# FOURCHANNEL_REAY_DRIVER.net
KiCad netlist of a schematic drawn in EAGLE
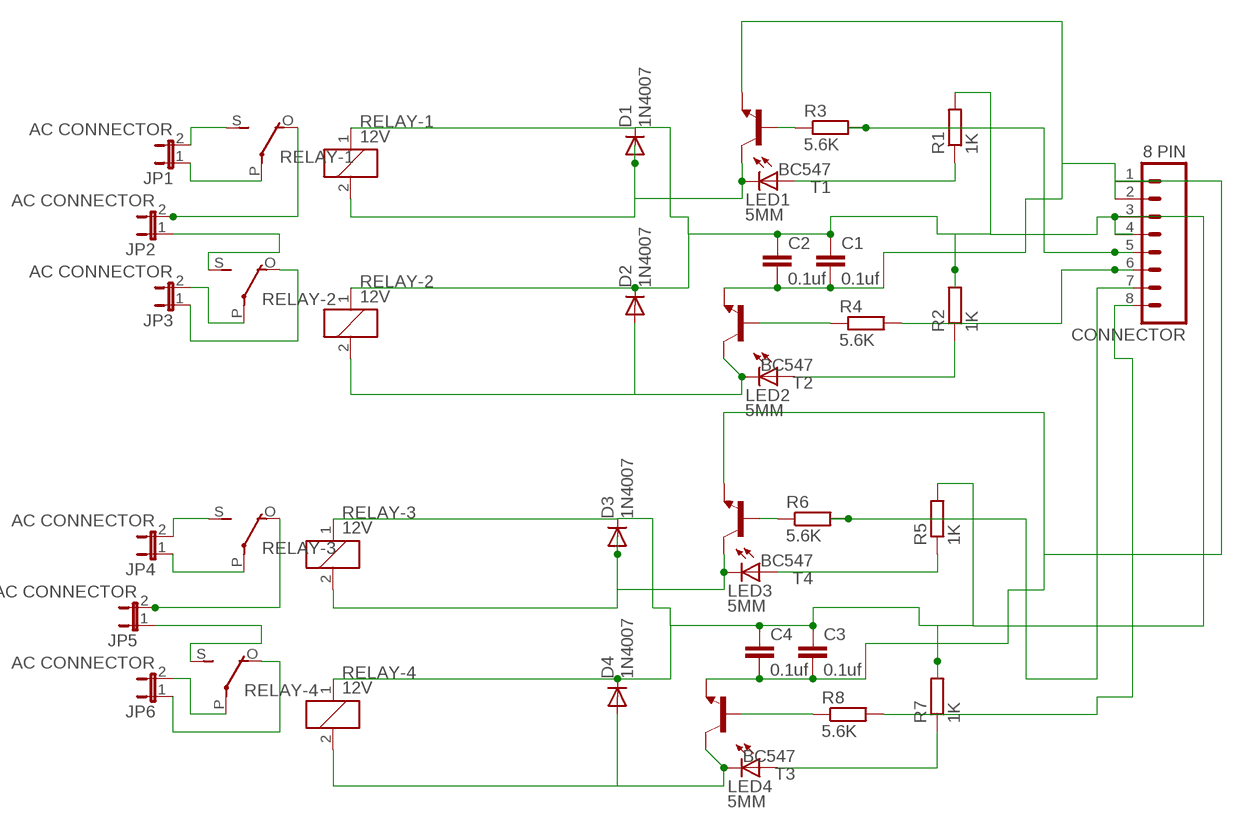
[diagram p0: schematic, sheet 1]

(export (version "E")
  (design (tool "Eeschema 10.0.6"))
  (components
    (comp (ref "C1")
      (value "0.1uf")
      (footprint "eagle-import:C2.5-3")
      (libsource (lib "eagle-import") (part "C2,5-3"))
    )
    (comp (ref "C2")
      (value "0.1uf")
      (footprint "eagle-import:C2.5-3")
      (libsource (lib "eagle-import") (part "C2,5-3"))
    )
    (comp (ref "C3")
      (value "0.1uf")
      (footprint "eagle-import:C2.5-3")
      (libsource (lib "eagle-import") (part "C2,5-3"))
    )
    (comp (ref "C4")
      (value "0.1uf")
      (footprint "eagle-import:C2.5-3")
      (libsource (lib "eagle-import") (part "C2,5-3"))
    )
    (comp (ref "CONNECTOR")
      (value "8 PIN")
      (footprint "eagle-import:08P")
      (libsource (lib "eagle-import") (part "M08"))
    )
    (comp (ref "D1")
      (value "1N4007")
      (footprint "eagle-import:DO41-10")
      (libsource (lib "eagle-import") (part "1N4004"))
    )
    (comp (ref "D2")
      (value "1N4007")
      (footprint "eagle-import:DO41-10")
      (libsource (lib "eagle-import") (part "1N4004"))
    )
    (comp (ref "D3")
      (value "1N4007")
      (footprint "eagle-import:DO41-10")
      (libsource (lib "eagle-import") (part "1N4004"))
    )
    (comp (ref "D4")
      (value "1N4007")
      (footprint "eagle-import:DO41-10")
      (libsource (lib "eagle-import") (part "1N4004"))
    )
    (comp (ref "JP1")
      (value "AC CONNECTOR")
      (footprint "eagle-import:JP1")
      (libsource (lib "eagle-import") (part "JP1E"))
    )
    (comp (ref "JP2")
      (value "AC CONNECTOR")
      (footprint "eagle-import:JP1")
      (libsource (lib "eagle-import") (part "JP1E"))
    )
    (comp (ref "JP3")
      (value "AC CONNECTOR")
      (footprint "eagle-import:JP1")
      (libsource (lib "eagle-import") (part "JP1E"))
    )
    (comp (ref "JP4")
      (value "AC CONNECTOR")
      (footprint "eagle-import:JP1")
      (libsource (lib "eagle-import") (part "JP1E"))
    )
    (comp (ref "JP5")
      (value "AC CONNECTOR")
      (footprint "eagle-import:JP1")
      (libsource (lib "eagle-import") (part "JP1E"))
    )
    (comp (ref "JP6")
      (value "AC CONNECTOR")
      (footprint "eagle-import:JP1")
      (libsource (lib "eagle-import") (part "JP1E"))
    )
    (comp (ref "LED1")
      (value "5MM")
      (footprint "eagle-import:LED5MM")
      (libsource (lib "eagle-import") (part "LED5MM"))
    )
    (comp (ref "LED2")
      (value "5MM")
      (footprint "eagle-import:LED5MM")
      (libsource (lib "eagle-import") (part "LED5MM"))
    )
    (comp (ref "LED3")
      (value "5MM")
      (footprint "eagle-import:LED5MM")
      (libsource (lib "eagle-import") (part "LED5MM"))
    )
    (comp (ref "LED4")
      (value "5MM")
      (footprint "eagle-import:LED5MM")
      (libsource (lib "eagle-import") (part "LED5MM"))
    )
    (comp (ref "R1")
      (value "1K")
      (footprint "eagle-import:0204_7")
      (libsource (lib "eagle-import") (part "R-EU_0204/7"))
    )
    (comp (ref "R2")
      (value "1K")
      (footprint "eagle-import:0204_7")
      (libsource (lib "eagle-import") (part "R-EU_0204/7"))
    )
    (comp (ref "R3")
      (value "5.6K")
      (footprint "eagle-import:0204_7")
      (libsource (lib "eagle-import") (part "R-EU_0204/7"))
    )
    (comp (ref "R4")
      (value "5.6K")
      (footprint "eagle-import:0204_7")
      (libsource (lib "eagle-import") (part "R-EU_0204/7"))
    )
    (comp (ref "R5")
      (value "1K")
      (footprint "eagle-import:0204_7")
      (libsource (lib "eagle-import") (part "R-EU_0204/7"))
    )
    (comp (ref "R6")
      (value "5.6K")
      (footprint "eagle-import:0204_7")
      (libsource (lib "eagle-import") (part "R-EU_0204/7"))
    )
    (comp (ref "R7")
      (value "1K")
      (footprint "eagle-import:0204_7")
      (libsource (lib "eagle-import") (part "R-EU_0204/7"))
    )
    (comp (ref "R8")
      (value "5.6K")
      (footprint "eagle-import:0204_7")
      (libsource (lib "eagle-import") (part "R-EU_0204/7"))
    )
    (comp (ref "RELAY-1")
      (value "12V")
      (footprint "eagle-import:G5LE")
      (libsource (lib "eagle-import") (part "G5L"))
    )
    (comp (ref "RELAY-2")
      (value "12V")
      (footprint "eagle-import:G5LE")
      (libsource (lib "eagle-import") (part "G5L"))
    )
    (comp (ref "RELAY-3")
      (value "12V")
      (footprint "eagle-import:G5LE")
      (libsource (lib "eagle-import") (part "G5L"))
    )
    (comp (ref "RELAY-4")
      (value "12V")
      (footprint "eagle-import:G5LE")
      (libsource (lib "eagle-import") (part "G5L"))
    )
    (comp (ref "T1")
      (value "BC547")
      (footprint "eagle-import:TO92")
      (libsource (lib "eagle-import") (part "BC547"))
    )
    (comp (ref "T2")
      (value "BC547")
      (footprint "eagle-import:TO92")
      (libsource (lib "eagle-import") (part "BC547"))
    )
    (comp (ref "T3")
      (value "BC547")
      (footprint "eagle-import:TO92")
      (libsource (lib "eagle-import") (part "BC547"))
    )
    (comp (ref "T4")
      (value "BC547")
      (footprint "eagle-import:TO92")
      (libsource (lib "eagle-import") (part "BC547"))
    )
  )
  (nets
    (net (code "1") (name "Net-(C1-Pad1)") (class "Default")
      (node (ref "C1") (pin "1") (pinfunction "1_1") (pintype "passive"))
      (node (ref "C2") (pin "1") (pinfunction "1_1") (pintype "passive"))
      (node (ref "C3") (pin "1") (pinfunction "1_1") (pintype "passive"))
      (node (ref "C4") (pin "1") (pinfunction "1_1") (pintype "passive"))
      (node (ref "CONNECTOR") (pin "3") (pinfunction "3_3") (pintype "passive"))
      (node (ref "CONNECTOR") (pin "4") (pinfunction "4_4") (pintype "passive"))
      (node (ref "D1") (pin "C") (pinfunction "C_C") (pintype "passive"))
      (node (ref "D2") (pin "C") (pinfunction "C_C") (pintype "passive"))
      (node (ref "D3") (pin "C") (pinfunction "C_C") (pintype "passive"))
      (node (ref "D4") (pin "C") (pinfunction "C_C") (pintype "passive"))
      (node (ref "R1") (pin "2") (pinfunction "2_2") (pintype "passive"))
      (node (ref "R2") (pin "2") (pinfunction "2_2") (pintype "passive"))
      (node (ref "R5") (pin "2") (pinfunction "2_2") (pintype "passive"))
      (node (ref "R7") (pin "2") (pinfunction "2_2") (pintype "passive"))
      (node (ref "RELAY-1") (pin "1") (pinfunction "1_1") (pintype "passive"))
      (node (ref "RELAY-2") (pin "1") (pinfunction "1_1") (pintype "passive"))
      (node (ref "RELAY-3") (pin "1") (pinfunction "1_1") (pintype "passive"))
      (node (ref "RELAY-4") (pin "1") (pinfunction "1_1") (pintype "passive"))
    )
    (net (code "2") (name "Net-(CONNECTOR-Pad5)") (class "Default")
      (node (ref "CONNECTOR") (pin "5") (pinfunction "5_5") (pintype "passive"))
      (node (ref "R3") (pin "2") (pinfunction "2_2") (pintype "passive"))
    )
    (net (code "3") (name "Net-(CONNECTOR-Pad6)") (class "Default")
      (node (ref "CONNECTOR") (pin "6") (pinfunction "6_6") (pintype "passive"))
      (node (ref "R4") (pin "2") (pinfunction "2_2") (pintype "passive"))
    )
    (net (code "4") (name "Net-(CONNECTOR-Pad7)") (class "Default")
      (node (ref "CONNECTOR") (pin "7") (pinfunction "7_7") (pintype "passive"))
      (node (ref "R6") (pin "2") (pinfunction "2_2") (pintype "passive"))
    )
    (net (code "5") (name "Net-(CONNECTOR-Pad8)") (class "Default")
      (node (ref "CONNECTOR") (pin "8") (pinfunction "8_8") (pintype "passive"))
      (node (ref "R8") (pin "2") (pinfunction "2_2") (pintype "passive"))
    )
    (net (code "6") (name "Net-(JP1-Pad1)") (class "Default")
      (node (ref "JP1") (pin "1") (pinfunction "1_1") (pintype "passive"))
      (node (ref "RELAY-1") (pin "P") (pinfunction "P_P") (pintype "passive"))
    )
    (net (code "7") (name "Net-(JP1-Pad2)") (class "Default")
      (node (ref "JP1") (pin "2") (pinfunction "2_2") (pintype "passive"))
      (node (ref "RELAY-1") (pin "S") (pinfunction "S_S") (pintype "passive"))
    )
    (net (code "8") (name "Net-(JP2-Pad1)") (class "Default")
      (node (ref "JP2") (pin "1") (pinfunction "1_1") (pintype "passive"))
      (node (ref "RELAY-2") (pin "S") (pinfunction "S_S") (pintype "passive"))
    )
    (net (code "9") (name "Net-(JP2-Pad2)") (class "Default")
      (node (ref "JP2") (pin "2") (pinfunction "2_2") (pintype "passive"))
      (node (ref "RELAY-1") (pin "O") (pinfunction "O_O") (pintype "passive"))
    )
    (net (code "10") (name "Net-(JP3-Pad1)") (class "Default")
      (node (ref "JP3") (pin "1") (pinfunction "1_1") (pintype "passive"))
      (node (ref "RELAY-2") (pin "O") (pinfunction "O_O") (pintype "passive"))
    )
    (net (code "11") (name "Net-(JP3-Pad2)") (class "Default")
      (node (ref "JP3") (pin "2") (pinfunction "2_2") (pintype "passive"))
      (node (ref "RELAY-2") (pin "P") (pinfunction "P_P") (pintype "passive"))
    )
    (net (code "12") (name "Net-(JP4-Pad1)") (class "Default")
      (node (ref "JP4") (pin "1") (pinfunction "1_1") (pintype "passive"))
      (node (ref "RELAY-3") (pin "P") (pinfunction "P_P") (pintype "passive"))
    )
    (net (code "13") (name "Net-(JP4-Pad2)") (class "Default")
      (node (ref "JP4") (pin "2") (pinfunction "2_2") (pintype "passive"))
      (node (ref "RELAY-3") (pin "S") (pinfunction "S_S") (pintype "passive"))
    )
    (net (code "14") (name "Net-(JP5-Pad1)") (class "Default")
      (node (ref "JP5") (pin "1") (pinfunction "1_1") (pintype "passive"))
      (node (ref "RELAY-4") (pin "S") (pinfunction "S_S") (pintype "passive"))
    )
    (net (code "15") (name "Net-(JP5-Pad2)") (class "Default")
      (node (ref "JP5") (pin "2") (pinfunction "2_2") (pintype "passive"))
      (node (ref "RELAY-3") (pin "O") (pinfunction "O_O") (pintype "passive"))
    )
    (net (code "16") (name "Net-(JP6-Pad1)") (class "Default")
      (node (ref "JP6") (pin "1") (pinfunction "1_1") (pintype "passive"))
      (node (ref "RELAY-4") (pin "O") (pinfunction "O_O") (pintype "passive"))
    )
    (net (code "17") (name "Net-(JP6-Pad2)") (class "Default")
      (node (ref "JP6") (pin "2") (pinfunction "2_2") (pintype "passive"))
      (node (ref "RELAY-4") (pin "P") (pinfunction "P_P") (pintype "passive"))
    )
    (net (code "18") (name "Net-(LED1-C)") (class "Default")
      (node (ref "D1") (pin "A") (pinfunction "A_A") (pintype "passive"))
      (node (ref "LED1") (pin "K") (pinfunction "C_K") (pintype "passive"))
      (node (ref "RELAY-1") (pin "2") (pinfunction "2_2") (pintype "passive"))
      (node (ref "T1") (pin "3") (pinfunction "C_3") (pintype "passive"))
    )
    (net (code "19") (name "Net-(LED1-PadA)") (class "Default")
      (node (ref "LED1") (pin "A") (pinfunction "A_A") (pintype "passive"))
      (node (ref "R1") (pin "1") (pinfunction "1_1") (pintype "passive"))
    )
    (net (code "20") (name "Net-(LED2-C)") (class "Default")
      (node (ref "D2") (pin "A") (pinfunction "A_A") (pintype "passive"))
      (node (ref "LED2") (pin "K") (pinfunction "C_K") (pintype "passive"))
      (node (ref "RELAY-2") (pin "2") (pinfunction "2_2") (pintype "passive"))
      (node (ref "T2") (pin "3") (pinfunction "C_3") (pintype "passive"))
    )
    (net (code "21") (name "Net-(LED2-PadA)") (class "Default")
      (node (ref "LED2") (pin "A") (pinfunction "A_A") (pintype "passive"))
      (node (ref "R2") (pin "1") (pinfunction "1_1") (pintype "passive"))
    )
    (net (code "22") (name "Net-(LED3-C)") (class "Default")
      (node (ref "D3") (pin "A") (pinfunction "A_A") (pintype "passive"))
      (node (ref "LED3") (pin "K") (pinfunction "C_K") (pintype "passive"))
      (node (ref "RELAY-3") (pin "2") (pinfunction "2_2") (pintype "passive"))
      (node (ref "T4") (pin "3") (pinfunction "C_3") (pintype "passive"))
    )
    (net (code "23") (name "Net-(LED3-PadA)") (class "Default")
      (node (ref "LED3") (pin "A") (pinfunction "A_A") (pintype "passive"))
      (node (ref "R5") (pin "1") (pinfunction "1_1") (pintype "passive"))
    )
    (net (code "24") (name "Net-(LED4-C)") (class "Default")
      (node (ref "D4") (pin "A") (pinfunction "A_A") (pintype "passive"))
      (node (ref "LED4") (pin "K") (pinfunction "C_K") (pintype "passive"))
      (node (ref "RELAY-4") (pin "2") (pinfunction "2_2") (pintype "passive"))
      (node (ref "T3") (pin "3") (pinfunction "C_3") (pintype "passive"))
    )
    (net (code "25") (name "Net-(LED4-PadA)") (class "Default")
      (node (ref "LED4") (pin "A") (pinfunction "A_A") (pintype "passive"))
      (node (ref "R7") (pin "1") (pinfunction "1_1") (pintype "passive"))
    )
    (net (code "26") (name "Net-(T1-B)") (class "Default")
      (node (ref "R3") (pin "1") (pinfunction "1_1") (pintype "passive"))
      (node (ref "T1") (pin "2") (pinfunction "B_2") (pintype "passive"))
    )
    (net (code "27") (name "Net-(T1-E)") (class "Default")
      (node (ref "C1") (pin "2") (pinfunction "2_2") (pintype "passive"))
      (node (ref "C2") (pin "2") (pinfunction "2_2") (pintype "passive"))
      (node (ref "C3") (pin "2") (pinfunction "2_2") (pintype "passive"))
      (node (ref "C4") (pin "2") (pinfunction "2_2") (pintype "passive"))
      (node (ref "CONNECTOR") (pin "1") (pinfunction "1_1") (pintype "passive"))
      (node (ref "CONNECTOR") (pin "2") (pinfunction "2_2") (pintype "passive"))
      (node (ref "T1") (pin "1") (pinfunction "E_1") (pintype "passive"))
      (node (ref "T2") (pin "1") (pinfunction "E_1") (pintype "passive"))
      (node (ref "T3") (pin "1") (pinfunction "E_1") (pintype "passive"))
      (node (ref "T4") (pin "1") (pinfunction "E_1") (pintype "passive"))
    )
    (net (code "28") (name "Net-(T2-B)") (class "Default")
      (node (ref "R4") (pin "1") (pinfunction "1_1") (pintype "passive"))
      (node (ref "T2") (pin "2") (pinfunction "B_2") (pintype "passive"))
    )
    (net (code "29") (name "Net-(T3-B)") (class "Default")
      (node (ref "R8") (pin "1") (pinfunction "1_1") (pintype "passive"))
      (node (ref "T3") (pin "2") (pinfunction "B_2") (pintype "passive"))
    )
    (net (code "30") (name "Net-(T4-B)") (class "Default")
      (node (ref "R6") (pin "1") (pinfunction "1_1") (pintype "passive"))
      (node (ref "T4") (pin "2") (pinfunction "B_2") (pintype "passive"))
    )
  )
)
